# way2.net
KiCad netlist of a schematic drawn in Altium Designer
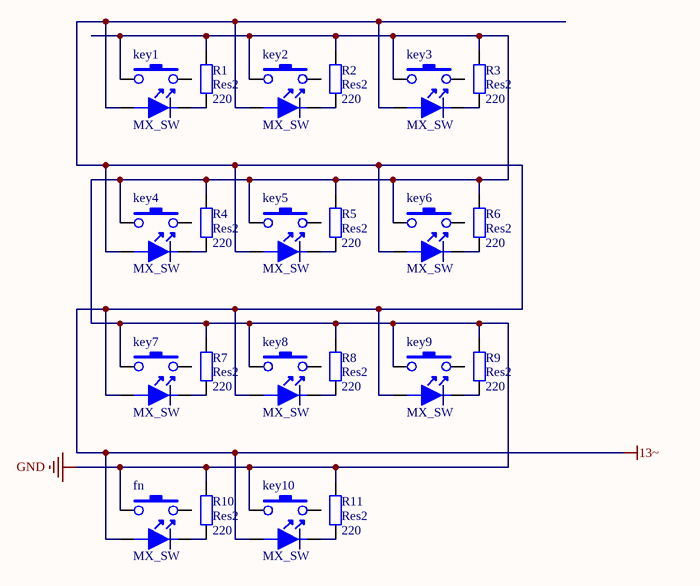
[diagram p0: way2.SchDoc]

(export (version "E")
  (design (tool "Eeschema 10.0.6"))
  (components
    (comp (ref "fn")
      (value "MX_SW")
      (footprint "MX_SW-2")
      (description "without Fixation pins  1-Pole w/LED")
      (libsource (lib "KeyBoard") (part "MX_SW-2"))
    )
    (comp (ref "key1")
      (value "MX_SW")
      (footprint "MX_SW-2")
      (description "without Fixation pins  1-Pole w/LED")
      (libsource (lib "KeyBoard") (part "MX_SW-2"))
    )
    (comp (ref "key2")
      (value "MX_SW")
      (footprint "MX_SW-2")
      (description "without Fixation pins  1-Pole w/LED")
      (libsource (lib "KeyBoard") (part "MX_SW-2"))
    )
    (comp (ref "key3")
      (value "MX_SW")
      (footprint "MX_SW-2")
      (description "without Fixation pins  1-Pole w/LED")
      (libsource (lib "KeyBoard") (part "MX_SW-2"))
    )
    (comp (ref "key4")
      (value "MX_SW")
      (footprint "MX_SW-2")
      (description "without Fixation pins  1-Pole w/LED")
      (libsource (lib "KeyBoard") (part "MX_SW-2"))
    )
    (comp (ref "key5")
      (value "MX_SW")
      (footprint "MX_SW-2")
      (description "without Fixation pins  1-Pole w/LED")
      (libsource (lib "KeyBoard") (part "MX_SW-2"))
    )
    (comp (ref "key6")
      (value "MX_SW")
      (footprint "MX_SW-2")
      (description "without Fixation pins  1-Pole w/LED")
      (libsource (lib "KeyBoard") (part "MX_SW-2"))
    )
    (comp (ref "key7")
      (value "MX_SW")
      (footprint "MX_SW-2")
      (description "without Fixation pins  1-Pole w/LED")
      (libsource (lib "KeyBoard") (part "MX_SW-2"))
    )
    (comp (ref "key8")
      (value "MX_SW")
      (footprint "MX_SW-2")
      (description "without Fixation pins  1-Pole w/LED")
      (libsource (lib "KeyBoard") (part "MX_SW-2"))
    )
    (comp (ref "key9")
      (value "MX_SW")
      (footprint "MX_SW-2")
      (description "without Fixation pins  1-Pole w/LED")
      (libsource (lib "KeyBoard") (part "MX_SW-2"))
    )
    (comp (ref "key10")
      (value "MX_SW")
      (footprint "MX_SW-2")
      (description "without Fixation pins  1-Pole w/LED")
      (libsource (lib "KeyBoard") (part "MX_SW-2"))
    )
    (comp (ref "R1")
      (value "Res2")
      (footprint "AXIAL-0.4")
      (description "Resistor")
      (fields (field (name "ALTIUM_VALUE") "220") (field (name "PUBLISHER") "Altium Limited"))
      (libsource (lib "") (part "Res2_1"))
    )
    (comp (ref "R2")
      (value "Res2")
      (footprint "AXIAL-0.4")
      (description "Resistor")
      (fields (field (name "ALTIUM_VALUE") "220") (field (name "PUBLISHER") "Altium Limited"))
      (libsource (lib "") (part "Res2_1"))
    )
    (comp (ref "R3")
      (value "Res2")
      (footprint "AXIAL-0.4")
      (description "Resistor")
      (fields (field (name "ALTIUM_VALUE") "220") (field (name "PUBLISHER") "Altium Limited"))
      (libsource (lib "Miscellaneous Devices") (part "Res2"))
    )
    (comp (ref "R4")
      (value "Res2")
      (footprint "AXIAL-0.4")
      (description "Resistor")
      (fields (field (name "ALTIUM_VALUE") "220") (field (name "PUBLISHER") "Altium Limited"))
      (libsource (lib "Miscellaneous Devices") (part "Res2"))
    )
    (comp (ref "R5")
      (value "Res2")
      (footprint "AXIAL-0.4")
      (description "Resistor")
      (fields (field (name "ALTIUM_VALUE") "220") (field (name "PUBLISHER") "Altium Limited"))
      (libsource (lib "Miscellaneous Devices") (part "Res2"))
    )
    (comp (ref "R6")
      (value "Res2")
      (footprint "AXIAL-0.4")
      (description "Resistor")
      (fields (field (name "ALTIUM_VALUE") "220") (field (name "PUBLISHER") "Altium Limited"))
      (libsource (lib "Miscellaneous Devices") (part "Res2"))
    )
    (comp (ref "R7")
      (value "Res2")
      (footprint "AXIAL-0.4")
      (description "Resistor")
      (fields (field (name "ALTIUM_VALUE") "220") (field (name "PUBLISHER") "Altium Limited"))
      (libsource (lib "Miscellaneous Devices") (part "Res2"))
    )
    (comp (ref "R8")
      (value "Res2")
      (footprint "AXIAL-0.4")
      (description "Resistor")
      (fields (field (name "ALTIUM_VALUE") "220") (field (name "PUBLISHER") "Altium Limited"))
      (libsource (lib "Miscellaneous Devices") (part "Res2"))
    )
    (comp (ref "R9")
      (value "Res2")
      (footprint "AXIAL-0.4")
      (description "Resistor")
      (fields (field (name "ALTIUM_VALUE") "220") (field (name "PUBLISHER") "Altium Limited"))
      (libsource (lib "Miscellaneous Devices") (part "Res2"))
    )
    (comp (ref "R10")
      (value "Res2")
      (footprint "AXIAL-0.4")
      (description "Resistor")
      (fields (field (name "ALTIUM_VALUE") "220") (field (name "PUBLISHER") "Altium Limited"))
      (libsource (lib "Miscellaneous Devices") (part "Res2"))
    )
    (comp (ref "R11")
      (value "Res2")
      (footprint "AXIAL-0.4")
      (description "Resistor")
      (fields (field (name "ALTIUM_VALUE") "220") (field (name "PUBLISHER") "Altium Limited"))
      (libsource (lib "Miscellaneous Devices") (part "Res2"))
    )
  )
  (nets
    (net (code "1") (name "13~") (class "Default")
      (node (ref "fn") (pin "3") (pinfunction "3_3") (pintype "passive"))
      (node (ref "key1") (pin "3") (pinfunction "3_3") (pintype "passive"))
      (node (ref "key10") (pin "3") (pinfunction "3_3") (pintype "passive"))
      (node (ref "key2") (pin "3") (pinfunction "3_3") (pintype "passive"))
      (node (ref "key3") (pin "3") (pinfunction "3_3") (pintype "passive"))
      (node (ref "key4") (pin "3") (pinfunction "3_3") (pintype "passive"))
      (node (ref "key5") (pin "3") (pinfunction "3_3") (pintype "passive"))
      (node (ref "key6") (pin "3") (pinfunction "3_3") (pintype "passive"))
      (node (ref "key7") (pin "3") (pinfunction "3_3") (pintype "passive"))
      (node (ref "key8") (pin "3") (pinfunction "3_3") (pintype "passive"))
      (node (ref "key9") (pin "3") (pinfunction "3_3") (pintype "passive"))
    )
    (net (code "2") (name "GND") (class "Default")
      (node (ref "R1") (pin "2") (pinfunction "2_2") (pintype "passive"))
      (node (ref "R10") (pin "1") (pinfunction "1_1") (pintype "passive"))
      (node (ref "R11") (pin "1") (pinfunction "1_1") (pintype "passive"))
      (node (ref "R2") (pin "2") (pinfunction "2_2") (pintype "passive"))
      (node (ref "R3") (pin "1") (pinfunction "1_1") (pintype "passive"))
      (node (ref "R4") (pin "1") (pinfunction "1_1") (pintype "passive"))
      (node (ref "R5") (pin "1") (pinfunction "1_1") (pintype "passive"))
      (node (ref "R6") (pin "1") (pinfunction "1_1") (pintype "passive"))
      (node (ref "R7") (pin "1") (pinfunction "1_1") (pintype "passive"))
      (node (ref "R8") (pin "1") (pinfunction "1_1") (pintype "passive"))
      (node (ref "R9") (pin "1") (pinfunction "1_1") (pintype "passive"))
      (node (ref "fn") (pin "1") (pinfunction "1_1") (pintype "passive"))
      (node (ref "key1") (pin "1") (pinfunction "1_1") (pintype "passive"))
      (node (ref "key10") (pin "1") (pinfunction "1_1") (pintype "passive"))
      (node (ref "key2") (pin "1") (pinfunction "1_1") (pintype "passive"))
      (node (ref "key3") (pin "1") (pinfunction "1_1") (pintype "passive"))
      (node (ref "key4") (pin "1") (pinfunction "1_1") (pintype "passive"))
      (node (ref "key5") (pin "1") (pinfunction "1_1") (pintype "passive"))
      (node (ref "key6") (pin "1") (pinfunction "1_1") (pintype "passive"))
      (node (ref "key7") (pin "1") (pinfunction "1_1") (pintype "passive"))
      (node (ref "key8") (pin "1") (pinfunction "1_1") (pintype "passive"))
      (node (ref "key9") (pin "1") (pinfunction "1_1") (pintype "passive"))
    )
    (net (code "3") (name "Net-(R1-Pad1)") (class "Default")
      (node (ref "R1") (pin "1") (pinfunction "1_1") (pintype "passive"))
      (node (ref "key1") (pin "4") (pinfunction "4_4") (pintype "passive"))
    )
    (net (code "4") (name "Net-(R2-Pad1)") (class "Default")
      (node (ref "R2") (pin "1") (pinfunction "1_1") (pintype "passive"))
      (node (ref "key2") (pin "4") (pinfunction "4_4") (pintype "passive"))
    )
    (net (code "5") (name "Net-(R3-Pad2)") (class "Default")
      (node (ref "R3") (pin "2") (pinfunction "2_2") (pintype "passive"))
      (node (ref "key3") (pin "4") (pinfunction "4_4") (pintype "passive"))
    )
    (net (code "6") (name "Net-(R4-Pad2)") (class "Default")
      (node (ref "R4") (pin "2") (pinfunction "2_2") (pintype "passive"))
      (node (ref "key4") (pin "4") (pinfunction "4_4") (pintype "passive"))
    )
    (net (code "7") (name "Net-(R5-Pad2)") (class "Default")
      (node (ref "R5") (pin "2") (pinfunction "2_2") (pintype "passive"))
      (node (ref "key5") (pin "4") (pinfunction "4_4") (pintype "passive"))
    )
    (net (code "8") (name "Net-(R6-Pad2)") (class "Default")
      (node (ref "R6") (pin "2") (pinfunction "2_2") (pintype "passive"))
      (node (ref "key6") (pin "4") (pinfunction "4_4") (pintype "passive"))
    )
    (net (code "9") (name "Net-(R7-Pad2)") (class "Default")
      (node (ref "R7") (pin "2") (pinfunction "2_2") (pintype "passive"))
      (node (ref "key7") (pin "4") (pinfunction "4_4") (pintype "passive"))
    )
    (net (code "10") (name "Net-(R8-Pad2)") (class "Default")
      (node (ref "R8") (pin "2") (pinfunction "2_2") (pintype "passive"))
      (node (ref "key8") (pin "4") (pinfunction "4_4") (pintype "passive"))
    )
    (net (code "11") (name "Net-(R9-Pad2)") (class "Default")
      (node (ref "R9") (pin "2") (pinfunction "2_2") (pintype "passive"))
      (node (ref "key9") (pin "4") (pinfunction "4_4") (pintype "passive"))
    )
    (net (code "12") (name "Net-(R10-Pad2)") (class "Default")
      (node (ref "R10") (pin "2") (pinfunction "2_2") (pintype "passive"))
      (node (ref "fn") (pin "4") (pinfunction "4_4") (pintype "passive"))
    )
    (net (code "13") (name "Net-(R11-Pad2)") (class "Default")
      (node (ref "R11") (pin "2") (pinfunction "2_2") (pintype "passive"))
      (node (ref "key10") (pin "4") (pinfunction "4_4") (pintype "passive"))
    )
    (net (code "14") (name "unconnected-(fn-Pad2)") (class "Default")
      (node (ref "fn") (pin "2") (pinfunction "2_2") (pintype "passive"))
    )
    (net (code "15") (name "unconnected-(key1-Pad2)") (class "Default")
      (node (ref "key1") (pin "2") (pinfunction "2_2") (pintype "passive"))
    )
    (net (code "16") (name "unconnected-(key2-Pad2)") (class "Default")
      (node (ref "key2") (pin "2") (pinfunction "2_2") (pintype "passive"))
    )
    (net (code "17") (name "unconnected-(key3-Pad2)") (class "Default")
      (node (ref "key3") (pin "2") (pinfunction "2_2") (pintype "passive"))
    )
    (net (code "18") (name "unconnected-(key4-Pad2)") (class "Default")
      (node (ref "key4") (pin "2") (pinfunction "2_2") (pintype "passive"))
    )
    (net (code "19") (name "unconnected-(key5-Pad2)") (class "Default")
      (node (ref "key5") (pin "2") (pinfunction "2_2") (pintype "passive"))
    )
    (net (code "20") (name "unconnected-(key6-Pad2)") (class "Default")
      (node (ref "key6") (pin "2") (pinfunction "2_2") (pintype "passive"))
    )
    (net (code "21") (name "unconnected-(key7-Pad2)") (class "Default")
      (node (ref "key7") (pin "2") (pinfunction "2_2") (pintype "passive"))
    )
    (net (code "22") (name "unconnected-(key8-Pad2)") (class "Default")
      (node (ref "key8") (pin "2") (pinfunction "2_2") (pintype "passive"))
    )
    (net (code "23") (name "unconnected-(key9-Pad2)") (class "Default")
      (node (ref "key9") (pin "2") (pinfunction "2_2") (pintype "passive"))
    )
    (net (code "24") (name "unconnected-(key10-Pad2)") (class "Default")
      (node (ref "key10") (pin "2") (pinfunction "2_2") (pintype "passive"))
    )
  )
)
